# power_reg.net
KiCad netlist of a schematic drawn in Altium Designer
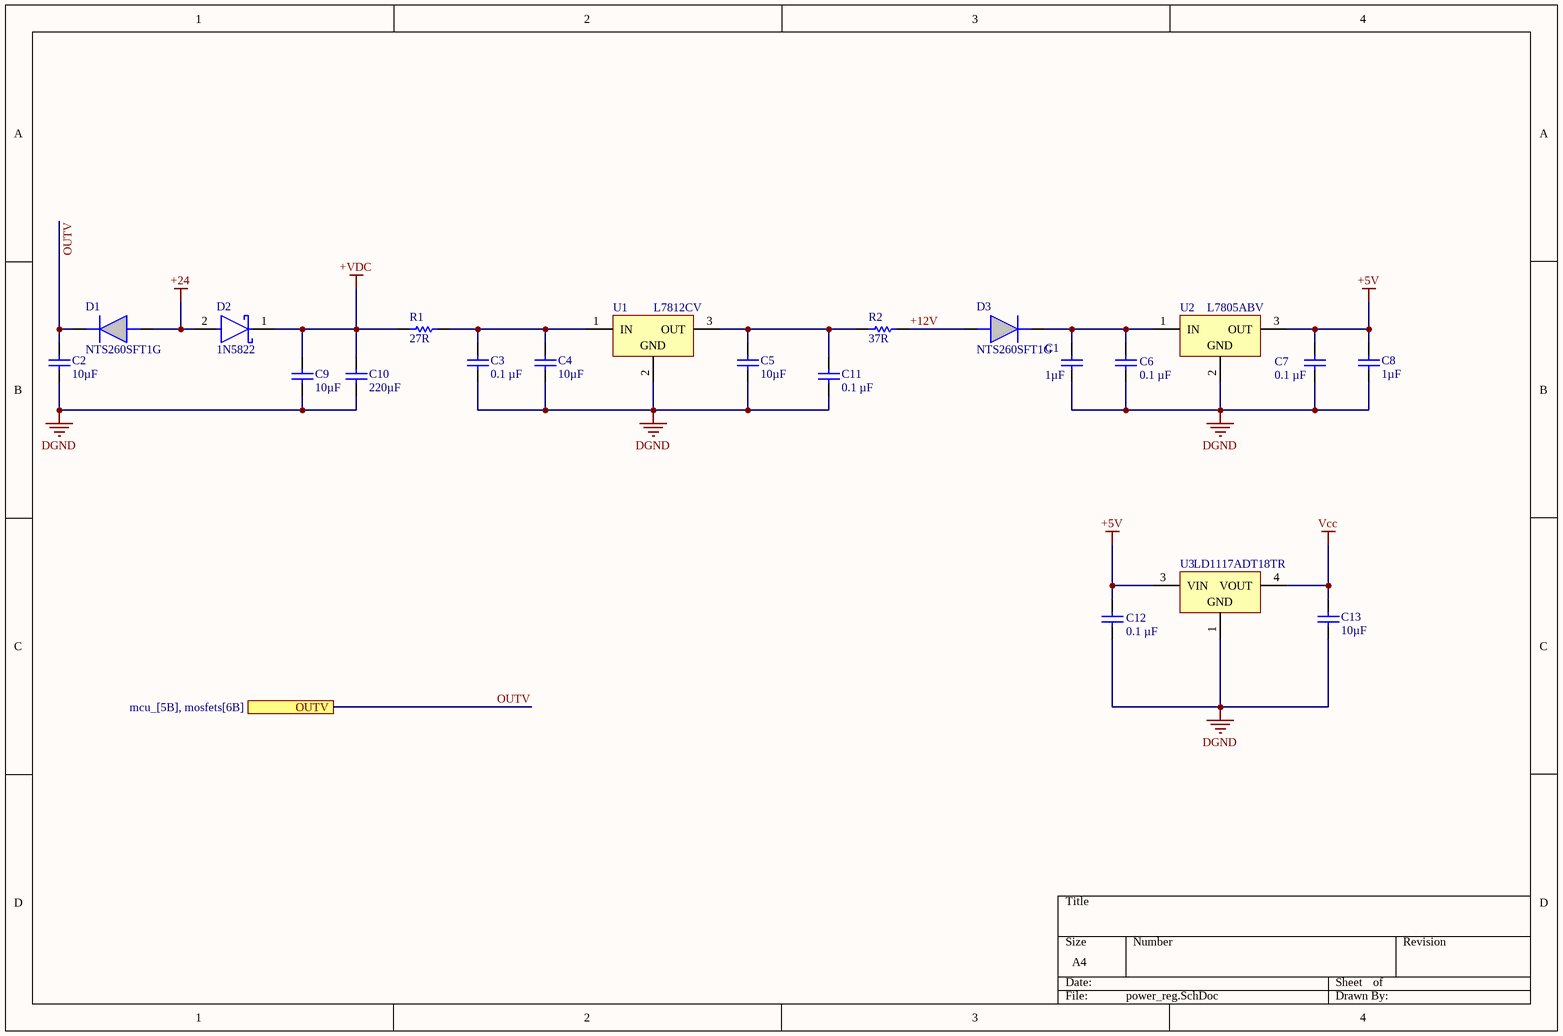
[diagram p0: power_reg.SchDoc]

(export (version "E")
  (design (tool "Eeschema 10.0.6"))
  (components
    (comp (ref "C1")
      (value "CAP CER 1UF 25V X7R 0603")
      (footprint "balloon:0603cap")
      (description "1 µF ±10% 25V Ceramic Capacitor X7R 0603 (1608 Metric)")
      (fields (field (name "MANUFACTURER") "Samsung Electro-Mechanics") (field (name "CAPACITANCE") "1µF"))
      (libsource (lib "Uroscan") (part "CAP CER 1UF 25V X7R 0603"))
    )
    (comp (ref "C2")
      (value "CAP CER 10UF 25V X5R 0805")
      (footprint "balloon:CAPC2012X140N - duplicate")
      (description "10 µF ±20% 25V Ceramic Capacitor X5R 0805 (2012 Metric)")
      (fields (field (name "CAPACITANCE") "10µF"))
      (libsource (lib "Uroscan") (part "CAP CER 10UF 25V X5R 0805"))
    )
    (comp (ref "C3")
      (value "CAP CER 0.1UF 25V X7R 0603")
      (footprint "0603cap")
      (description "0.1 µF ±5% 25V Ceramic Capacitor X7R 0603 (1608 Metric)")
      (fields (field (name "CAPACITANCE") "0.1 µF"))
      (libsource (lib "Uroscan") (part "CAP CER 0.1UF 25V X7R 0603"))
    )
    (comp (ref "C4")
      (value "CAP CER 10UF 25V X5R 0805")
      (footprint "balloon:0603cap")
      (description "10 µF ±20% 25V Ceramic Capacitor X5R 0805 (2012 Metric)")
      (fields (field (name "CAPACITANCE") "10µF"))
      (libsource (lib "Uroscan") (part "CAP CER 10UF 25V X5R 0805"))
    )
    (comp (ref "C5")
      (value "CAP CER 10UF 25V X5R 0805")
      (footprint "balloon:CAPC2012X140N - duplicate")
      (description "10 µF ±20% 25V Ceramic Capacitor X5R 0805 (2012 Metric)")
      (fields (field (name "CAPACITANCE") "10µF"))
      (libsource (lib "Uroscan") (part "CAP CER 10UF 25V X5R 0805"))
    )
    (comp (ref "C6")
      (value "CAP CER 0.1UF 25V X7R 0603")
      (footprint "0603cap")
      (description "0.1 µF ±5% 25V Ceramic Capacitor X7R 0603 (1608 Metric)")
      (fields (field (name "CAPACITANCE") "0.1 µF"))
      (libsource (lib "Uroscan") (part "CAP CER 0.1UF 25V X7R 0603"))
    )
    (comp (ref "C7")
      (value "CAP CER 0.1UF 25V X7R 0603")
      (footprint "0603cap")
      (description "0.1 µF ±5% 25V Ceramic Capacitor X7R 0603 (1608 Metric)")
      (fields (field (name "CAPACITANCE") "0.1 µF"))
      (libsource (lib "Uroscan") (part "CAP CER 0.1UF 25V X7R 0603"))
    )
    (comp (ref "C8")
      (value "CAP CER 1UF 25V X7R 0603")
      (footprint "balloon:0603cap")
      (description "1 µF ±10% 25V Ceramic Capacitor X7R 0603 (1608 Metric)")
      (fields (field (name "MANUFACTURER") "Samsung Electro-Mechanics") (field (name "CAPACITANCE") "1µF"))
      (libsource (lib "Uroscan") (part "CAP CER 1UF 25V X7R 0603"))
    )
    (comp (ref "C9")
      (value "CAP CER 10UF 25V X5R 0805")
      (footprint "balloon:CAPC2012X140N - duplicate")
      (description "10 µF ±20% 25V Ceramic Capacitor X5R 0805 (2012 Metric)")
      (fields (field (name "CAPACITANCE") "10µF"))
      (libsource (lib "Uroscan") (part "CAP CER 10UF 25V X5R 0805"))
    )
    (comp (ref "C10")
      (value "CAP CER 10UF 25V X5R 0805")
      (footprint "balloon:CAPC2012X140N - duplicate")
      (description "10 µF ±20% 25V Ceramic Capacitor X5R 0805 (2012 Metric)")
      (fields (field (name "CAPACITANCE") "220µF"))
      (libsource (lib "Uroscan") (part "CAP CER 10UF 25V X5R 0805"))
    )
    (comp (ref "C11")
      (value "CAP CER 0.1UF 25V X7R 0603")
      (footprint "0603cap")
      (description "0.1 µF ±5% 25V Ceramic Capacitor X7R 0603 (1608 Metric)")
      (fields (field (name "CAPACITANCE") "0.1 µF"))
      (libsource (lib "Uroscan") (part "CAP CER 0.1UF 25V X7R 0603"))
    )
    (comp (ref "C12")
      (value "CAP CER 0.1UF 25V X7R 0603")
      (footprint "0603cap")
      (description "0.1 µF ±5% 25V Ceramic Capacitor X7R 0603 (1608 Metric)")
      (fields (field (name "CAPACITANCE") "0.1 µF"))
      (libsource (lib "Uroscan") (part "CAP CER 0.1UF 25V X7R 0603"))
    )
    (comp (ref "C13")
      (value "CAP CER 10UF 25V X5R 0805")
      (footprint "balloon:CAPC2012X140N")
      (description "10 µF ±20% 25V Ceramic Capacitor X5R 0805 (2012 Metric)")
      (fields (field (name "CAPACITANCE") "10µF"))
      (libsource (lib "Uroscan") (part "CAP CER 10UF 25V X5R 0805"))
    )
    (comp (ref "D1")
      (value "NTS260SFT1G")
      (footprint "SODFL3616X98N")
      (fields (field (name "MOUSER PART NUMBER") "863-NTS260SFT1G"))
      (libsource (lib "Uroscan") (part "NTS260SFT1G"))
    )
    (comp (ref "D2")
      (value "1N5822")
      (footprint "FP-DO-201AD-MFG")
      (description "DIODE SCHOTTKY 40V 3A DO201AD")
      (fields
        (field (name "OCTOPART") "https://octopart.com/1n5822-stmicroelectronics-323225")
        (field (name "MANUFACTURER") "STMicroelectronics")
      )
      (libsource (lib "Altium Content Vault") (part "1d6ec82d83fb6aee721767c19dac4b9"))
    )
    (comp (ref "D3")
      (value "NTS260SFT1G")
      (footprint "SODFL3616X98N")
      (fields (field (name "MOUSER PART NUMBER") "863-NTS260SFT1G"))
      (libsource (lib "Uroscan") (part "NTS260SFT1G"))
    )
    (comp (ref "R1")
      (value "RC0603JR-0727RL")
      (footprint "balloon:0603 RES")
      (description "RES 27 OHM 5% 1/10W 0603")
      (fields (field (name "MANUFACTURER") "YAGEO") (field (name "RESISTANCE") "27R"))
      (libsource (lib "Uroscan") (part "RES 27 OHM 5% 1/10W 0603"))
    )
    (comp (ref "R2")
      (value "RC0603JR-0727RL")
      (footprint "0603 RES")
      (description "RES 27 OHM 5% 1/10W 0603")
      (fields (field (name "MANUFACTURER") "YAGEO") (field (name "RESISTANCE") "37R"))
      (libsource (lib "Uroscan") (part "RES 27 OHM 5% 1/10W 0603"))
    )
    (comp (ref "U1")
      (value "L7812CV")
      (footprint "TO220")
      (description "Positive Voltage Regulator, 12V, 3-Pin TO-220")
      (libsource (lib "Altium Content Vault") (part "PM-REG-L4940-SIL3"))
    )
    (comp (ref "U2")
      (value "L7805ABV")
      (footprint "TO220")
      (description "Positive Voltage Regulator, 5V, 3-Pin TO-220")
      (libsource (lib "Altium Content Vault") (part "PM-REG-L4940-SIL3"))
    )
    (comp (ref "U3")
      (value "LD1117ADT18TR")
      (footprint "TO-252_N")
      (description "1A, Low Drop Positive Voltage Regulator, 1.8V, 3-Pin DPAK, Tape and Reel")
      (libsource (lib "Altium Content Vault") (part "PM-REG-LD1117-SOT3"))
    )
  )
  (nets
    (net (code "1") (name "+5V") (class "Default")
      (node (ref "C12") (pin "2") (pinfunction "2_2") (pintype "passive"))
      (node (ref "C7") (pin "2") (pinfunction "2_2") (pintype "passive"))
      (node (ref "C8") (pin "2") (pinfunction "2_2") (pintype "passive"))
      (node (ref "U2") (pin "3") (pinfunction "OUT_3") (pintype "power_in"))
      (node (ref "U3") (pin "3") (pinfunction "VIN_3") (pintype "power_in"))
    )
    (net (code "2") (name "+24") (class "Default")
      (node (ref "D1") (pin "2") (pinfunction "A_2") (pintype "passive"))
      (node (ref "D2") (pin "2") (pinfunction "A_2") (pintype "passive"))
    )
    (net (code "3") (name "+VDC") (class "Default")
      (node (ref "C10") (pin "2") (pinfunction "2_2") (pintype "passive"))
      (node (ref "C9") (pin "2") (pinfunction "2_2") (pintype "passive"))
      (node (ref "D2") (pin "1") (pinfunction "C_1") (pintype "passive"))
      (node (ref "R1") (pin "1") (pinfunction "1_1") (pintype "passive"))
    )
    (net (code "4") (name "/+12V") (class "Default")
      (node (ref "D3") (pin "2") (pinfunction "A_2") (pintype "passive"))
      (node (ref "R2") (pin "1") (pinfunction "1_1") (pintype "passive"))
    )
    (net (code "5") (name "/OUTV") (class "Default")
      (node (ref "C2") (pin "2") (pinfunction "2_2") (pintype "passive"))
      (node (ref "D1") (pin "1") (pinfunction "K_1") (pintype "passive"))
    )
    (net (code "6") (name "DGND") (class "Default")
      (node (ref "C1") (pin "1") (pinfunction "1_1") (pintype "passive"))
      (node (ref "C10") (pin "1") (pinfunction "1_1") (pintype "passive"))
      (node (ref "C11") (pin "1") (pinfunction "1_1") (pintype "passive"))
      (node (ref "C12") (pin "1") (pinfunction "1_1") (pintype "passive"))
      (node (ref "C13") (pin "1") (pinfunction "1_1") (pintype "passive"))
      (node (ref "C2") (pin "1") (pinfunction "1_1") (pintype "passive"))
      (node (ref "C3") (pin "1") (pinfunction "1_1") (pintype "passive"))
      (node (ref "C4") (pin "1") (pinfunction "1_1") (pintype "passive"))
      (node (ref "C5") (pin "1") (pinfunction "1_1") (pintype "passive"))
      (node (ref "C6") (pin "1") (pinfunction "1_1") (pintype "passive"))
      (node (ref "C7") (pin "1") (pinfunction "1_1") (pintype "passive"))
      (node (ref "C8") (pin "1") (pinfunction "1_1") (pintype "passive"))
      (node (ref "C9") (pin "1") (pinfunction "1_1") (pintype "passive"))
      (node (ref "U1") (pin "2") (pinfunction "GND_2") (pintype "power_in"))
      (node (ref "U2") (pin "2") (pinfunction "GND_2") (pintype "power_in"))
      (node (ref "U3") (pin "1") (pinfunction "GND_1") (pintype "power_in"))
    )
    (net (code "7") (name "Net-(D3-K)") (class "Default")
      (node (ref "C1") (pin "2") (pinfunction "2_2") (pintype "passive"))
      (node (ref "C6") (pin "2") (pinfunction "2_2") (pintype "passive"))
      (node (ref "D3") (pin "1") (pinfunction "K_1") (pintype "passive"))
      (node (ref "U2") (pin "1") (pinfunction "IN_1") (pintype "power_in"))
    )
    (net (code "8") (name "Net-(U1-IN)") (class "Default")
      (node (ref "C3") (pin "2") (pinfunction "2_2") (pintype "passive"))
      (node (ref "C4") (pin "2") (pinfunction "2_2") (pintype "passive"))
      (node (ref "R1") (pin "2") (pinfunction "2_2") (pintype "passive"))
      (node (ref "U1") (pin "1") (pinfunction "IN_1") (pintype "power_in"))
    )
    (net (code "9") (name "Net-(U1-OUT)") (class "Default")
      (node (ref "C11") (pin "2") (pinfunction "2_2") (pintype "passive"))
      (node (ref "C5") (pin "2") (pinfunction "2_2") (pintype "passive"))
      (node (ref "R2") (pin "2") (pinfunction "2_2") (pintype "passive"))
      (node (ref "U1") (pin "3") (pinfunction "OUT_3") (pintype "power_in"))
    )
    (net (code "10") (name "Vcc") (class "Default")
      (node (ref "C13") (pin "2") (pinfunction "2_2") (pintype "passive"))
      (node (ref "U3") (pin "4") (pinfunction "VOUT_4") (pintype "power_in"))
    )
  )
)
